# serializer.net
KiCad netlist of a schematic drawn in Altium Designer
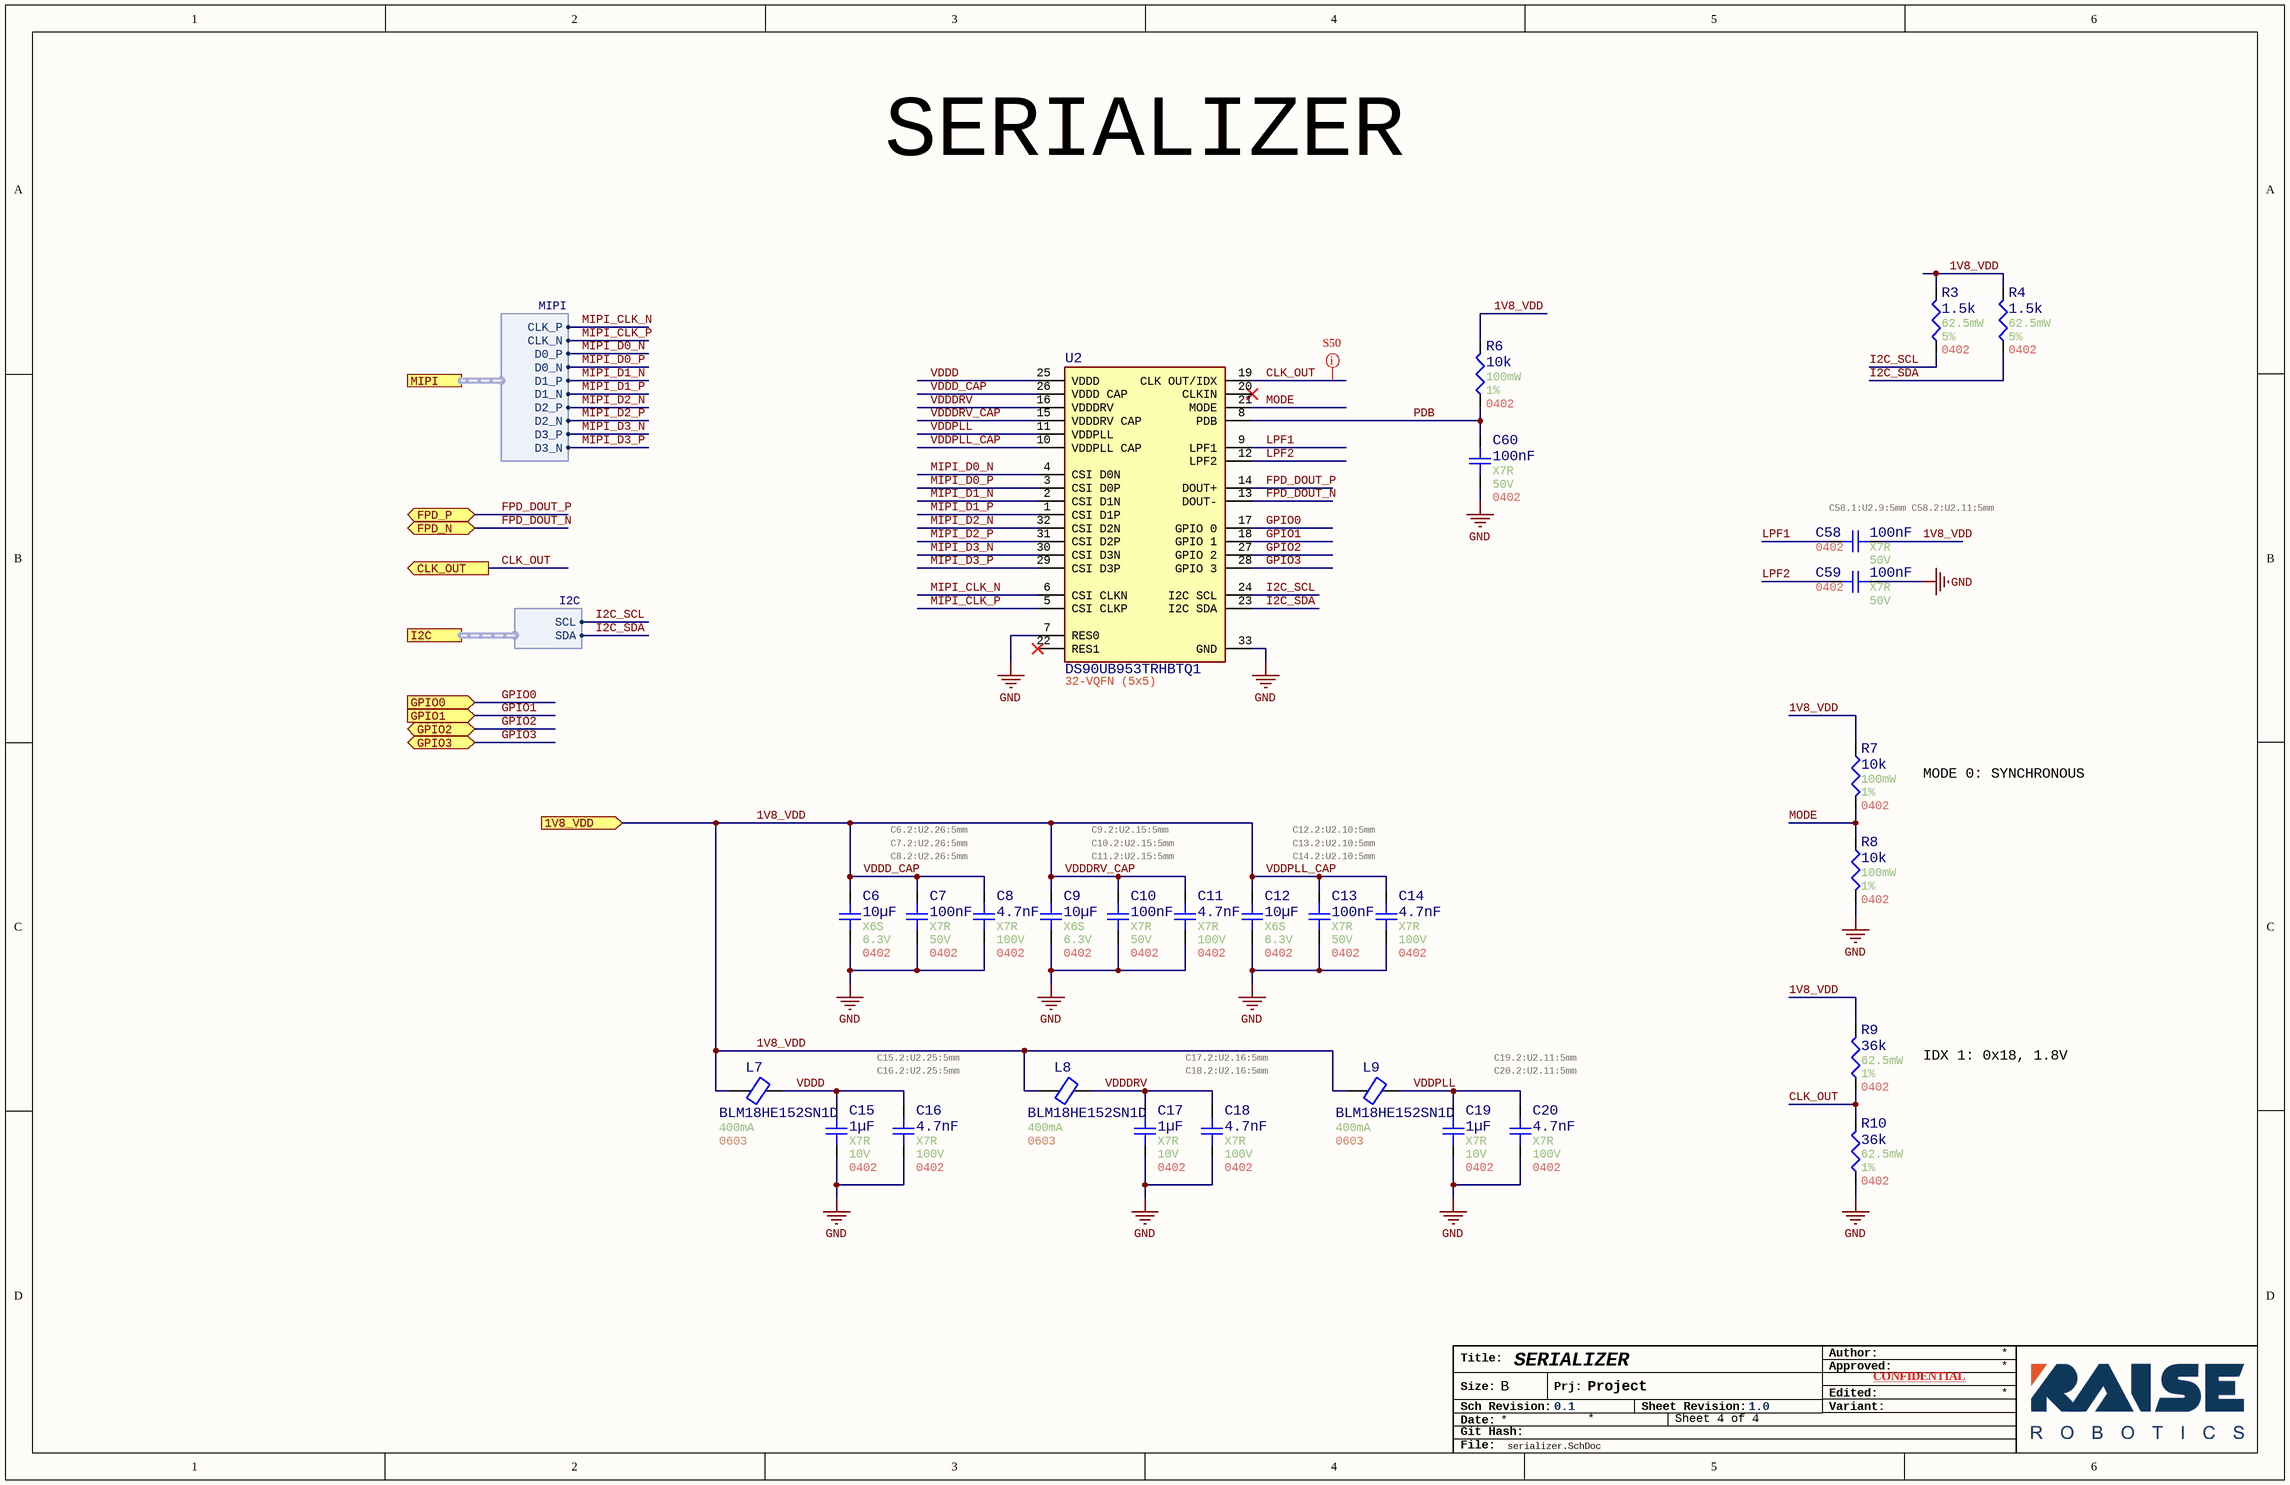
[diagram p0: serializer.SchDoc]

(export (version "E")
  (design (tool "Eeschema 10.0.6"))
  (components
    (comp (ref "C6")
      (value "10µF")
      (footprint "Generic 0402 capacitor")
      (description "Multilayer Ceramic Capacitors MLCC - SMD/SMT 0402 10uF 6.3VDC 20% X6S AEC-Q200")
      (fields
        (field (name "TEMPERATURE COEFFICIENT") "X6S")
        (field (name "VOLTAGE RATING") "6.3V")
        (field (name "CASE/PACKAGE") "0402")
        (field (name "TOLERANCE") "20%")
        (field (name "PLACENEAR") "C6.2:U2.26:5mm")
        (field (name "Comment") "GRT155C80J106ME13J")
      )
      (libsource (lib "Raise Robotics") (part "Unpolarized Capacitor"))
    )
    (comp (ref "C7")
      (value "100nF")
      (footprint "Generic 0402 capacitor")
      (fields
        (field (name "TEMPERATURE COEFFICIENT") "X7R")
        (field (name "VOLTAGE RATING") "50V")
        (field (name "CASE/PACKAGE") "0402")
        (field (name "TOLERANCE") "10%")
        (field (name "PLACENEAR") "C7.2:U2.26:5mm")
        (field (name "Comment") "GRT155R71H104KE01D")
      )
      (libsource (lib "Raise Robotics") (part "Unpolarized Capacitor"))
    )
    (comp (ref "C8")
      (value "4.7nF")
      (footprint "Generic 0402 capacitor")
      (fields
        (field (name "TEMPERATURE COEFFICIENT") "X7R")
        (field (name "VOLTAGE RATING") "100V")
        (field (name "CASE/PACKAGE") "0402")
        (field (name "TOLERANCE") "10%")
        (field (name "PLACENEAR") "C8.2:U2.26:5mm")
        (field (name "Comment") "GCM155R72A472KA37D")
      )
      (libsource (lib "Raise Robotics") (part "Unpolarized Capacitor"))
    )
    (comp (ref "C9")
      (value "10µF")
      (footprint "Generic 0402 capacitor")
      (description "Multilayer Ceramic Capacitors MLCC - SMD/SMT 0402 10uF 6.3VDC 20% X6S AEC-Q200")
      (fields
        (field (name "TEMPERATURE COEFFICIENT") "X6S")
        (field (name "VOLTAGE RATING") "6.3V")
        (field (name "CASE/PACKAGE") "0402")
        (field (name "TOLERANCE") "20%")
        (field (name "PLACENEAR") "C9.2:U2.15:5mm")
        (field (name "Comment") "GRT155C80J106ME13J")
      )
      (libsource (lib "Raise Robotics") (part "Unpolarized Capacitor"))
    )
    (comp (ref "C10")
      (value "100nF")
      (footprint "Generic 0402 capacitor")
      (fields
        (field (name "TEMPERATURE COEFFICIENT") "X7R")
        (field (name "VOLTAGE RATING") "50V")
        (field (name "CASE/PACKAGE") "0402")
        (field (name "TOLERANCE") "10%")
        (field (name "PLACENEAR") "C10.2:U2.15:5mm")
        (field (name "Comment") "GRT155R71H104KE01D")
      )
      (libsource (lib "Raise Robotics") (part "Unpolarized Capacitor"))
    )
    (comp (ref "C11")
      (value "4.7nF")
      (footprint "Generic 0402 capacitor")
      (fields
        (field (name "TEMPERATURE COEFFICIENT") "X7R")
        (field (name "VOLTAGE RATING") "100V")
        (field (name "CASE/PACKAGE") "0402")
        (field (name "TOLERANCE") "10%")
        (field (name "PLACENEAR") "C11.2:U2.15:5mm")
        (field (name "Comment") "GCM155R72A472KA37D")
      )
      (libsource (lib "Raise Robotics") (part "Unpolarized Capacitor"))
    )
    (comp (ref "C12")
      (value "10µF")
      (footprint "Generic 0402 capacitor")
      (description "Multilayer Ceramic Capacitors MLCC - SMD/SMT 0402 10uF 6.3VDC 20% X6S AEC-Q200")
      (fields
        (field (name "TEMPERATURE COEFFICIENT") "X6S")
        (field (name "VOLTAGE RATING") "6.3V")
        (field (name "CASE/PACKAGE") "0402")
        (field (name "TOLERANCE") "20%")
        (field (name "PLACENEAR") "C12.2:U2.10:5mm")
        (field (name "Comment") "GRT155C80J106ME13J")
      )
      (libsource (lib "Raise Robotics") (part "Unpolarized Capacitor"))
    )
    (comp (ref "C13")
      (value "100nF")
      (footprint "Generic 0402 capacitor")
      (fields
        (field (name "TEMPERATURE COEFFICIENT") "X7R")
        (field (name "VOLTAGE RATING") "50V")
        (field (name "CASE/PACKAGE") "0402")
        (field (name "TOLERANCE") "10%")
        (field (name "PLACENEAR") "C13.2:U2.10:5mm")
        (field (name "Comment") "GRT155R71H104KE01D")
      )
      (libsource (lib "Raise Robotics") (part "Unpolarized Capacitor"))
    )
    (comp (ref "C14")
      (value "4.7nF")
      (footprint "Generic 0402 capacitor")
      (fields
        (field (name "TEMPERATURE COEFFICIENT") "X7R")
        (field (name "VOLTAGE RATING") "100V")
        (field (name "CASE/PACKAGE") "0402")
        (field (name "TOLERANCE") "10%")
        (field (name "PLACENEAR") "C14.2:U2.10:5mm")
        (field (name "Comment") "GCM155R72A472KA37D")
      )
      (libsource (lib "Raise Robotics") (part "Unpolarized Capacitor"))
    )
    (comp (ref "C15")
      (value "1µF")
      (footprint "Generic 0402 capacitor")
      (description "Cap Cer 1UF 20V X7T 0402")
      (fields
        (field (name "TEMPERATURE COEFFICIENT") "X7R")
        (field (name "VOLTAGE RATING") "10V")
        (field (name "CASE/PACKAGE") "0402")
        (field (name "TOLERANCE") "20%")
        (field (name "PLACENEAR") "C15.2:U2.25:5mm")
        (field (name "Comment") "MAASL105CD7105MFCA01")
      )
      (libsource (lib "Raise Robotics") (part "Unpolarized Capacitor"))
    )
    (comp (ref "C16")
      (value "4.7nF")
      (footprint "Generic 0402 capacitor")
      (fields
        (field (name "TEMPERATURE COEFFICIENT") "X7R")
        (field (name "VOLTAGE RATING") "100V")
        (field (name "CASE/PACKAGE") "0402")
        (field (name "TOLERANCE") "10%")
        (field (name "PLACENEAR") "C16.2:U2.25:5mm")
        (field (name "Comment") "GCM155R72A472KA37D")
      )
      (libsource (lib "Raise Robotics") (part "Unpolarized Capacitor"))
    )
    (comp (ref "C17")
      (value "1µF")
      (footprint "Generic 0402 capacitor")
      (description "Cap Cer 1UF 20V X7T 0402")
      (fields
        (field (name "TEMPERATURE COEFFICIENT") "X7R")
        (field (name "VOLTAGE RATING") "10V")
        (field (name "CASE/PACKAGE") "0402")
        (field (name "TOLERANCE") "20%")
        (field (name "PLACENEAR") "C17.2:U2.16:5mm")
        (field (name "Comment") "MAASL105CD7105MFCA01")
      )
      (libsource (lib "Raise Robotics") (part "Unpolarized Capacitor"))
    )
    (comp (ref "C18")
      (value "4.7nF")
      (footprint "Generic 0402 capacitor")
      (fields
        (field (name "TEMPERATURE COEFFICIENT") "X7R")
        (field (name "VOLTAGE RATING") "100V")
        (field (name "CASE/PACKAGE") "0402")
        (field (name "TOLERANCE") "10%")
        (field (name "PLACENEAR") "C18.2:U2.16:5mm")
        (field (name "Comment") "GCM155R72A472KA37D")
      )
      (libsource (lib "Raise Robotics") (part "Unpolarized Capacitor"))
    )
    (comp (ref "C19")
      (value "1µF")
      (footprint "Generic 0402 capacitor")
      (description "Cap Cer 1UF 20V X7T 0402")
      (fields
        (field (name "TEMPERATURE COEFFICIENT") "X7R")
        (field (name "VOLTAGE RATING") "10V")
        (field (name "CASE/PACKAGE") "0402")
        (field (name "TOLERANCE") "20%")
        (field (name "PLACENEAR") "C19.2:U2.11:5mm")
        (field (name "Comment") "MAASL105CD7105MFCA01")
      )
      (libsource (lib "Raise Robotics") (part "Unpolarized Capacitor"))
    )
    (comp (ref "C20")
      (value "4.7nF")
      (footprint "Generic 0402 capacitor")
      (fields
        (field (name "TEMPERATURE COEFFICIENT") "X7R")
        (field (name "VOLTAGE RATING") "100V")
        (field (name "CASE/PACKAGE") "0402")
        (field (name "TOLERANCE") "10%")
        (field (name "PLACENEAR") "C20.2:U2.11:5mm")
        (field (name "Comment") "GCM155R72A472KA37D")
      )
      (libsource (lib "Raise Robotics") (part "Unpolarized Capacitor"))
    )
    (comp (ref "C58")
      (value "100nF")
      (footprint "Generic 0402 capacitor")
      (fields
        (field (name "TEMPERATURE COEFFICIENT") "X7R")
        (field (name "VOLTAGE RATING") "50V")
        (field (name "CASE/PACKAGE") "0402")
        (field (name "TOLERANCE") "10%")
        (field (name "PLACENEAR") "C58.1:U2.9:5mm\nC58.2:U2.11:5mm")
        (field (name "Comment") "GRT155R71H104KE01D")
      )
      (libsource (lib "Raise Robotics") (part "Unpolarized Capacitor"))
    )
    (comp (ref "C59")
      (value "100nF")
      (footprint "Generic 0402 capacitor")
      (fields
        (field (name "TEMPERATURE COEFFICIENT") "X7R")
        (field (name "VOLTAGE RATING") "50V")
        (field (name "CASE/PACKAGE") "0402")
        (field (name "TOLERANCE") "10%")
        (field (name "Comment") "GRT155R71H104KE01D")
      )
      (libsource (lib "Raise Robotics") (part "Unpolarized Capacitor"))
    )
    (comp (ref "C60")
      (value "100nF")
      (footprint "Generic 0402 capacitor")
      (fields
        (field (name "TEMPERATURE COEFFICIENT") "X7R")
        (field (name "VOLTAGE RATING") "50V")
        (field (name "CASE/PACKAGE") "0402")
        (field (name "TOLERANCE") "10%")
        (field (name "Comment") "GRT155R71H104KE01D")
      )
      (libsource (lib "Raise Robotics") (part "Unpolarized Capacitor"))
    )
    (comp (ref "L7")
      (value "BLM18HE152SN1D")
      (footprint "0603_1.6x0.8x0.8mm_IND")
      (description "Ferrite Beads Multi-Layer 1.5KOhm 25% 100MHz 500mA 500mOhm DCR 0603 T/R")
      (fields
        (field (name "CURRENT RATING") "400mA")
        (field (name "CASE/PACKAGE") "0603")
        (field (name "TOLERANCE") "25%")
      )
      (libsource (lib "Raise Robotics") (part "Generic 2 pin ferrite bead"))
    )
    (comp (ref "L8")
      (value "BLM18HE152SN1D")
      (footprint "0603_1.6x0.8x0.8mm_IND")
      (description "Ferrite Beads Multi-Layer 1.5KOhm 25% 100MHz 500mA 500mOhm DCR 0603 T/R")
      (fields
        (field (name "CURRENT RATING") "400mA")
        (field (name "CASE/PACKAGE") "0603")
        (field (name "TOLERANCE") "25%")
      )
      (libsource (lib "Raise Robotics") (part "Generic 2 pin ferrite bead"))
    )
    (comp (ref "L9")
      (value "BLM18HE152SN1D")
      (footprint "0603_1.6x0.8x0.8mm_IND")
      (description "Ferrite Beads Multi-Layer 1.5KOhm 25% 100MHz 500mA 500mOhm DCR 0603 T/R")
      (fields
        (field (name "CURRENT RATING") "400mA")
        (field (name "CASE/PACKAGE") "0603")
        (field (name "TOLERANCE") "25%")
      )
      (libsource (lib "Raise Robotics") (part "Generic 2 pin ferrite bead"))
    )
    (comp (ref "R3")
      (value "1.5k")
      (footprint "Generic 0402 Resistor")
      (description "Res Thick Film 0402 1.5K Ohm 5% 0.063W ±100ppm/°C Molded SMD Paper T/R")
      (fields
        (field (name "POWER") "62.5mW")
        (field (name "TOLERANCE") "5%")
        (field (name "CASE/PACKAGE") "0402")
        (field (name "Comment") "RMCF0402JT1K50")
      )
      (libsource (lib "Raise Robotics") (part "Resistor"))
    )
    (comp (ref "R4")
      (value "1.5k")
      (footprint "Generic 0402 Resistor")
      (description "Res Thick Film 0402 1.5K Ohm 5% 0.063W ±100ppm/°C Molded SMD Paper T/R")
      (fields
        (field (name "POWER") "62.5mW")
        (field (name "TOLERANCE") "5%")
        (field (name "CASE/PACKAGE") "0402")
        (field (name "Comment") "RMCF0402JT1K50")
      )
      (libsource (lib "Raise Robotics") (part "Resistor"))
    )
    (comp (ref "R6")
      (value "10k")
      (footprint "Generic 0402 Resistor")
      (description "Fixed Resistor, Thin Film, 0.1W, 10000ohm, 50V, 1% +/-Tol, 100ppm/Cel, Surface Mount, 0402")
      (fields
        (field (name "POWER") "100mW")
        (field (name "TOLERANCE") "1%")
        (field (name "CASE/PACKAGE") "0402")
        (field (name "MANUFACTURER PART NUMBER") "Blank")
        (field (name "Comment") "RNCP0402FTD10K0")
      )
      (libsource (lib "Raise Robotics") (part "Resistor"))
    )
    (comp (ref "R7")
      (value "10k")
      (footprint "Generic 0402 Resistor")
      (description "Fixed Resistor, Thin Film, 0.1W, 10000ohm, 50V, 1% +/-Tol, 100ppm/Cel, Surface Mount, 0402")
      (fields
        (field (name "POWER") "100mW")
        (field (name "TOLERANCE") "1%")
        (field (name "CASE/PACKAGE") "0402")
        (field (name "MANUFACTURER PART NUMBER") "Blank")
        (field (name "Comment") "RNCP0402FTD10K0")
      )
      (libsource (lib "Raise Robotics") (part "Resistor"))
    )
    (comp (ref "R8")
      (value "10k")
      (footprint "Generic 0402 Resistor")
      (description "Fixed Resistor, Thin Film, 0.1W, 10000ohm, 50V, 1% +/-Tol, 100ppm/Cel, Surface Mount, 0402")
      (fields
        (field (name "POWER") "100mW")
        (field (name "TOLERANCE") "1%")
        (field (name "CASE/PACKAGE") "0402")
        (field (name "MANUFACTURER PART NUMBER") "Blank")
        (field (name "Comment") "RNCP0402FTD10K0")
      )
      (libsource (lib "Raise Robotics") (part "Resistor"))
    )
    (comp (ref "R9")
      (value "36k")
      (footprint "Generic 0402 Resistor")
      (fields
        (field (name "POWER") "62.5mW")
        (field (name "TOLERANCE") "1%")
        (field (name "CASE/PACKAGE") "0402")
        (field (name "Comment") "AC0402FR-0736KL")
      )
      (libsource (lib "Raise Robotics") (part "Resistor"))
    )
    (comp (ref "R10")
      (value "36k")
      (footprint "Generic 0402 Resistor")
      (fields
        (field (name "POWER") "62.5mW")
        (field (name "TOLERANCE") "1%")
        (field (name "CASE/PACKAGE") "0402")
        (field (name "Comment") "AC0402FR-0736KL")
      )
      (libsource (lib "Raise Robotics") (part "Resistor"))
    )
    (comp (ref "U2")
      (value "DS90UB953TRHBTQ1")
      (footprint "VQFN-32_5x5x1.0mm_P0.5mm")
      (description "2 MP MIPI® CSI-2 FPD-Link III serializer for 2MP/60fps cameras & radar 32-VQFN -40 to 105")
      (fields (field (name "CASE/PACKAGE") "32-VQFN (5x5)"))
      (libsource (lib "Raise Robotics") (part "DS90UB953TRHBTQ1"))
    )
  )
  (nets
    (net (code "3") (name "/1V8_VDD") (class "Default")
      (node (ref "C10") (pin "2") (pinfunction "2_2") (pintype "passive"))
      (node (ref "C11") (pin "2") (pinfunction "2_2") (pintype "passive"))
      (node (ref "C12") (pin "2") (pinfunction "2_2") (pintype "passive"))
      (node (ref "C13") (pin "2") (pinfunction "2_2") (pintype "passive"))
      (node (ref "C14") (pin "2") (pinfunction "2_2") (pintype "passive"))
      (node (ref "C58") (pin "2") (pinfunction "2_2") (pintype "passive"))
      (node (ref "C6") (pin "2") (pinfunction "2_2") (pintype "passive"))
      (node (ref "C7") (pin "2") (pinfunction "2_2") (pintype "passive"))
      (node (ref "C8") (pin "2") (pinfunction "2_2") (pintype "passive"))
      (node (ref "C9") (pin "2") (pinfunction "2_2") (pintype "passive"))
      (node (ref "L7") (pin "1") (pinfunction "1_1") (pintype "passive"))
      (node (ref "L8") (pin "1") (pinfunction "1_1") (pintype "passive"))
      (node (ref "L9") (pin "1") (pinfunction "1_1") (pintype "passive"))
      (node (ref "R3") (pin "2") (pinfunction "2_2") (pintype "passive"))
      (node (ref "R4") (pin "2") (pinfunction "2_2") (pintype "passive"))
      (node (ref "R6") (pin "2") (pinfunction "2_2") (pintype "passive"))
      (node (ref "R7") (pin "1") (pinfunction "1_1") (pintype "passive"))
      (node (ref "R9") (pin "2") (pinfunction "2_2") (pintype "passive"))
      (node (ref "U2") (pin "10") (pinfunction "VDDPLL_CAP_10") (pintype "passive"))
      (node (ref "U2") (pin "15") (pinfunction "VDDDRV_CAP_15") (pintype "passive"))
      (node (ref "U2") (pin "26") (pinfunction "VDDD_CAP_26") (pintype "passive"))
    )
    (net (code "4") (name "/CLK_OUT") (class "Default")
      (node (ref "R10") (pin "2") (pinfunction "2_2") (pintype "passive"))
      (node (ref "R9") (pin "1") (pinfunction "1_1") (pintype "passive"))
      (node (ref "U2") (pin "19") (pinfunction "CLK_OUT/IDX_19") (pintype "passive"))
    )
    (net (code "5") (name "/FPD_DOUT_N") (class "Default")
      (node (ref "U2") (pin "13") (pinfunction "DOUT-_13") (pintype "passive"))
    )
    (net (code "6") (name "/FPD_DOUT_P") (class "Default")
      (node (ref "U2") (pin "14") (pinfunction "DOUT+_14") (pintype "passive"))
    )
    (net (code "7") (name "/GPIO0") (class "Default")
      (node (ref "U2") (pin "17") (pinfunction "GPIO_0_17") (pintype "passive"))
    )
    (net (code "8") (name "/GPIO1") (class "Default")
      (node (ref "U2") (pin "18") (pinfunction "GPIO_1_18") (pintype "passive"))
    )
    (net (code "9") (name "/GPIO2") (class "Default")
      (node (ref "U2") (pin "27") (pinfunction "GPIO_2_27") (pintype "passive"))
    )
    (net (code "10") (name "/GPIO3") (class "Default")
      (node (ref "U2") (pin "28") (pinfunction "GPIO_3_28") (pintype "passive"))
    )
    (net (code "11") (name "/I2C_SCL") (class "Default")
      (node (ref "R3") (pin "1") (pinfunction "1_1") (pintype "passive"))
      (node (ref "U2") (pin "24") (pinfunction "I2C_SCL_24") (pintype "passive"))
    )
    (net (code "12") (name "/I2C_SDA") (class "Default")
      (node (ref "R4") (pin "1") (pinfunction "1_1") (pintype "passive"))
      (node (ref "U2") (pin "23") (pinfunction "I2C_SDA_23") (pintype "passive"))
    )
    (net (code "13") (name "/LPF1") (class "Default")
      (node (ref "C58") (pin "1") (pinfunction "1_1") (pintype "passive"))
      (node (ref "U2") (pin "9") (pinfunction "LPF1_9") (pintype "passive"))
    )
    (net (code "14") (name "/LPF2") (class "Default")
      (node (ref "C59") (pin "1") (pinfunction "1_1") (pintype "passive"))
      (node (ref "U2") (pin "12") (pinfunction "LPF2_12") (pintype "passive"))
    )
    (net (code "15") (name "/MIPI_CLK_N") (class "Default")
      (node (ref "U2") (pin "6") (pinfunction "CSI_CLKN_6") (pintype "passive"))
    )
    (net (code "16") (name "/MIPI_CLK_P") (class "Default")
      (node (ref "U2") (pin "5") (pinfunction "CSI_CLKP_5") (pintype "passive"))
    )
    (net (code "17") (name "/MIPI_D0_N") (class "Default")
      (node (ref "U2") (pin "4") (pinfunction "CSI_D0N_4") (pintype "passive"))
    )
    (net (code "18") (name "/MIPI_D0_P") (class "Default")
      (node (ref "U2") (pin "3") (pinfunction "CSI_D0P_3") (pintype "passive"))
    )
    (net (code "19") (name "/MIPI_D1_N") (class "Default")
      (node (ref "U2") (pin "2") (pinfunction "CSI_D1N_2") (pintype "passive"))
    )
    (net (code "20") (name "/MIPI_D1_P") (class "Default")
      (node (ref "U2") (pin "1") (pinfunction "CSI_D1P_1") (pintype "passive"))
    )
    (net (code "21") (name "/MIPI_D2_N") (class "Default")
      (node (ref "U2") (pin "32") (pinfunction "CSI_D2N_32") (pintype "passive"))
    )
    (net (code "22") (name "/MIPI_D2_P") (class "Default")
      (node (ref "U2") (pin "31") (pinfunction "CSI_D2P_31") (pintype "passive"))
    )
    (net (code "23") (name "/MIPI_D3_N") (class "Default")
      (node (ref "U2") (pin "30") (pinfunction "CSI_D3N_30") (pintype "passive"))
    )
    (net (code "24") (name "/MIPI_D3_P") (class "Default")
      (node (ref "U2") (pin "29") (pinfunction "CSI_D3P_29") (pintype "passive"))
    )
    (net (code "25") (name "/MODE") (class "Default")
      (node (ref "R7") (pin "2") (pinfunction "2_2") (pintype "passive"))
      (node (ref "R8") (pin "1") (pinfunction "1_1") (pintype "passive"))
      (node (ref "U2") (pin "21") (pinfunction "MODE_21") (pintype "passive"))
    )
    (net (code "26") (name "/PDB") (class "Default")
      (node (ref "C60") (pin "1") (pinfunction "1_1") (pintype "passive"))
      (node (ref "R6") (pin "1") (pinfunction "1_1") (pintype "passive"))
      (node (ref "U2") (pin "8") (pinfunction "PDB_8") (pintype "passive"))
    )
    (net (code "27") (name "/VDDD") (class "Default")
      (node (ref "C15") (pin "2") (pinfunction "2_2") (pintype "passive"))
      (node (ref "C16") (pin "2") (pinfunction "2_2") (pintype "passive"))
      (node (ref "L7") (pin "2") (pinfunction "2_2") (pintype "passive"))
      (node (ref "U2") (pin "25") (pinfunction "VDDD_25") (pintype "passive"))
    )
    (net (code "28") (name "/VDDDRV") (class "Default")
      (node (ref "C17") (pin "2") (pinfunction "2_2") (pintype "passive"))
      (node (ref "C18") (pin "2") (pinfunction "2_2") (pintype "passive"))
      (node (ref "L8") (pin "2") (pinfunction "2_2") (pintype "passive"))
      (node (ref "U2") (pin "16") (pinfunction "VDDDRV_16") (pintype "passive"))
    )
    (net (code "29") (name "/VDDPLL") (class "Default")
      (node (ref "C19") (pin "2") (pinfunction "2_2") (pintype "passive"))
      (node (ref "C20") (pin "2") (pinfunction "2_2") (pintype "passive"))
      (node (ref "L9") (pin "2") (pinfunction "2_2") (pintype "passive"))
      (node (ref "U2") (pin "11") (pinfunction "VDDPLL_11") (pintype "passive"))
    )
    (net (code "32") (name "GND") (class "Default")
      (node (ref "C10") (pin "1") (pinfunction "1_1") (pintype "passive"))
      (node (ref "C11") (pin "1") (pinfunction "1_1") (pintype "passive"))
      (node (ref "C12") (pin "1") (pinfunction "1_1") (pintype "passive"))
      (node (ref "C13") (pin "1") (pinfunction "1_1") (pintype "passive"))
      (node (ref "C14") (pin "1") (pinfunction "1_1") (pintype "passive"))
      (node (ref "C15") (pin "1") (pinfunction "1_1") (pintype "passive"))
      (node (ref "C16") (pin "1") (pinfunction "1_1") (pintype "passive"))
      (node (ref "C17") (pin "1") (pinfunction "1_1") (pintype "passive"))
      (node (ref "C18") (pin "1") (pinfunction "1_1") (pintype "passive"))
      (node (ref "C19") (pin "1") (pinfunction "1_1") (pintype "passive"))
      (node (ref "C20") (pin "1") (pinfunction "1_1") (pintype "passive"))
      (node (ref "C59") (pin "2") (pinfunction "2_2") (pintype "passive"))
      (node (ref "C6") (pin "1") (pinfunction "1_1") (pintype "passive"))
      (node (ref "C60") (pin "2") (pinfunction "2_2") (pintype "passive"))
      (node (ref "C7") (pin "1") (pinfunction "1_1") (pintype "passive"))
      (node (ref "C8") (pin "1") (pinfunction "1_1") (pintype "passive"))
      (node (ref "C9") (pin "1") (pinfunction "1_1") (pintype "passive"))
      (node (ref "R10") (pin "1") (pinfunction "1_1") (pintype "passive"))
      (node (ref "R8") (pin "2") (pinfunction "2_2") (pintype "passive"))
      (node (ref "U2") (pin "33") (pinfunction "GND_33") (pintype "passive"))
      (node (ref "U2") (pin "7") (pinfunction "RES0_7") (pintype "passive"))
    )
    (net (code "33") (name "unconnected-(U2-CLKIN-Pad20)") (class "Default")
      (node (ref "U2") (pin "20") (pinfunction "CLKIN_20") (pintype "passive+no_connect"))
    )
    (net (code "34") (name "unconnected-(U2-RES1-Pad22)") (class "Default")
      (node (ref "U2") (pin "22") (pinfunction "RES1_22") (pintype "passive+no_connect"))
    )
  )
)
